# HUB-USB.net
KiCad netlist of a schematic drawn in Altium Designer
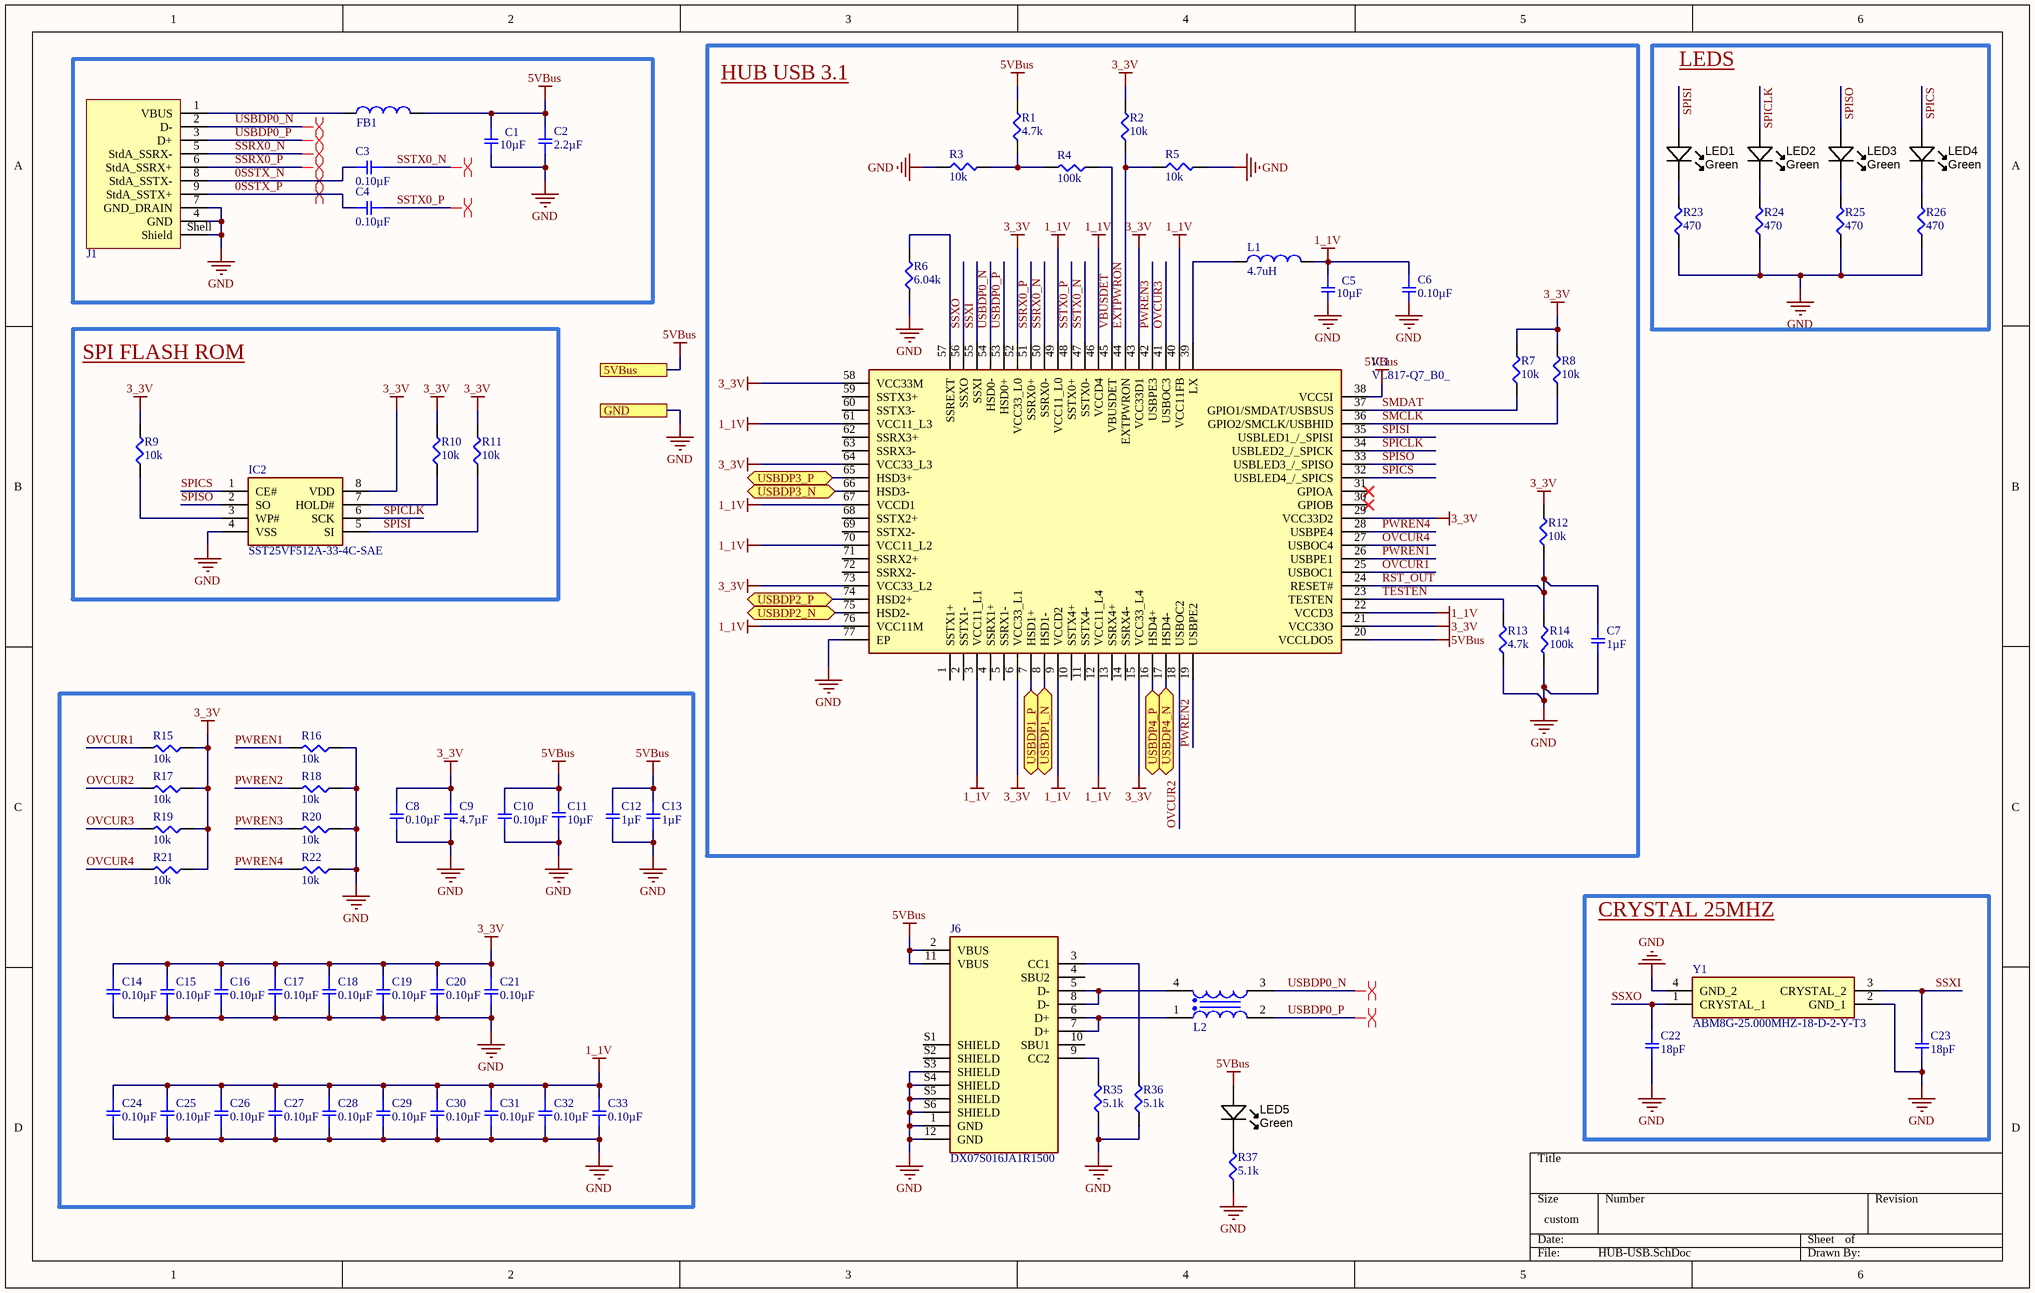
[diagram p0: HUB-USB.SchDoc]

(export (version "E")
  (design (tool "Eeschema 10.0.6"))
  (components
    (comp (ref "C1")
      (value "10µF")
      (footprint "SMD-0603C")
      (description "CAP CER 10UF 16V X6S 0603")
      (fields
        (field (name "PART NUMBER") "GRT188C81C106ME13D")
        (field (name "DIGI-KEY PART NUMBER") "490-12286-1-ND")
      )
      (libsource (lib "cap_murata") (part "CAPACITOR"))
    )
    (comp (ref "C2")
      (value "2.2µF")
      (footprint "SMD-0603C")
      (description "CAP CER 2.2UF 16V X6S 0603")
      (fields
        (field (name "PART NUMBER") "GRT188C81C225KE13D")
        (field (name "DIGI-KEY PART NUMBER") "490-12287-1-ND")
      )
      (libsource (lib "cap_murata") (part "CAPACITOR"))
    )
    (comp (ref "C3")
      (value "0.10µF")
      (footprint "SMD-0402C")
      (description "CAP CER 0.1UF 16V X7R 0402")
      (fields
        (field (name "PART NUMBER") "GCM155R71C104KA55J")
        (field (name "DIGI-KEY PART NUMBER") "490-7998-1-ND")
      )
      (libsource (lib "cap_murata") (part "CAPACITOR"))
    )
    (comp (ref "C4")
      (value "0.10µF")
      (footprint "SMD-0402C")
      (description "CAP CER 0.1UF 16V X7R 0402")
      (fields
        (field (name "PART NUMBER") "GCM155R71C104KA55J")
        (field (name "DIGI-KEY PART NUMBER") "490-7998-1-ND")
      )
      (libsource (lib "cap_murata") (part "CAPACITOR"))
    )
    (comp (ref "C5")
      (value "10µF")
      (footprint "SMD-0603C")
      (description "CAP CER 10UF 16V X6S 0603")
      (fields
        (field (name "PART NUMBER") "GRT188C81C106ME13D")
        (field (name "DIGI-KEY PART NUMBER") "490-12286-1-ND")
      )
      (libsource (lib "cap_murata") (part "CAPACITOR"))
    )
    (comp (ref "C6")
      (value "0.10µF")
      (footprint "SMD-0402C")
      (description "CAP CER 0.1UF 16V X7R 0402")
      (fields
        (field (name "PART NUMBER") "GCM155R71C104KA55J")
        (field (name "DIGI-KEY PART NUMBER") "490-7998-1-ND")
      )
      (libsource (lib "cap_murata") (part "CAPACITOR"))
    )
    (comp (ref "C7")
      (value "1µF")
      (footprint "SMD-0402C")
      (description "CAP CER 1UF 25V X5R 0402")
      (fields
        (field (name "PART NUMBER") "GRM155R61E105MA12D")
        (field (name "DIGI-KEY PART NUMBER") "490-10018-1-ND")
      )
      (libsource (lib "cap_murata") (part "CAPACITOR"))
    )
    (comp (ref "C8")
      (value "0.10µF")
      (footprint "SMD-0402C")
      (description "CAP CER 0.1UF 16V X7R 0402")
      (fields
        (field (name "PART NUMBER") "GCM155R71C104KA55J")
        (field (name "DIGI-KEY PART NUMBER") "490-7998-1-ND")
      )
      (libsource (lib "cap_murata") (part "CAPACITOR"))
    )
    (comp (ref "C9")
      (value "4.7µF")
      (footprint "SMD-0402C")
      (description "CAP CER 4.7UF 10V X5R 0402")
      (fields
        (field (name "PART NUMBER") "ZRB15XR61A475KE01D")
        (field (name "DIGI-KEY PART NUMBER") "490-13252-1-ND")
      )
      (libsource (lib "cap_murata") (part "CAPACITOR"))
    )
    (comp (ref "C10")
      (value "0.10µF")
      (footprint "SMD-0402C")
      (description "CAP CER 0.1UF 16V X7R 0402")
      (fields
        (field (name "PART NUMBER") "GCM155R71C104KA55J")
        (field (name "DIGI-KEY PART NUMBER") "490-7998-1-ND")
      )
      (libsource (lib "cap_murata") (part "CAPACITOR"))
    )
    (comp (ref "C11")
      (value "10µF")
      (footprint "SMD-0805C")
      (description "CAP CER 10UF 16V X6S 0805")
      (fields
        (field (name "PART NUMBER") "GRT21BC81C106KE01L")
        (field (name "DIGI-KEY PART NUMBER") "490-12343-1-ND")
      )
      (libsource (lib "cap_murata") (part "CAPACITOR"))
    )
    (comp (ref "C12")
      (value "1µF")
      (footprint "SMD-0402C")
      (description "CAP CER 1UF 25V X5R 0402")
      (fields
        (field (name "PART NUMBER") "GRM155R61E105MA12D")
        (field (name "DIGI-KEY PART NUMBER") "490-10018-1-ND")
      )
      (libsource (lib "cap_murata") (part "CAPACITOR"))
    )
    (comp (ref "C13")
      (value "1µF")
      (footprint "SMD-0402C")
      (description "CAP CER 1UF 25V X5R 0402")
      (fields
        (field (name "PART NUMBER") "GRM155R61E105MA12D")
        (field (name "DIGI-KEY PART NUMBER") "490-10018-1-ND")
      )
      (libsource (lib "cap_murata") (part "CAPACITOR"))
    )
    (comp (ref "C14")
      (value "0.10µF")
      (footprint "SMD-0402C")
      (description "CAP CER 0.1UF 16V X7R 0402")
      (fields
        (field (name "PART NUMBER") "GCM155R71C104KA55J")
        (field (name "DIGI-KEY PART NUMBER") "490-7998-1-ND")
      )
      (libsource (lib "cap_murata") (part "CAPACITOR"))
    )
    (comp (ref "C15")
      (value "0.10µF")
      (footprint "SMD-0402C")
      (description "CAP CER 0.1UF 16V X7R 0402")
      (fields
        (field (name "PART NUMBER") "GCM155R71C104KA55J")
        (field (name "DIGI-KEY PART NUMBER") "490-7998-1-ND")
      )
      (libsource (lib "cap_murata") (part "CAPACITOR"))
    )
    (comp (ref "C16")
      (value "0.10µF")
      (footprint "SMD-0402C")
      (description "CAP CER 0.1UF 16V X7R 0402")
      (fields
        (field (name "PART NUMBER") "GCM155R71C104KA55J")
        (field (name "DIGI-KEY PART NUMBER") "490-7998-1-ND")
      )
      (libsource (lib "cap_murata") (part "CAPACITOR"))
    )
    (comp (ref "C17")
      (value "0.10µF")
      (footprint "SMD-0402C")
      (description "CAP CER 0.1UF 16V X7R 0402")
      (fields
        (field (name "PART NUMBER") "GCM155R71C104KA55J")
        (field (name "DIGI-KEY PART NUMBER") "490-7998-1-ND")
      )
      (libsource (lib "cap_murata") (part "CAPACITOR"))
    )
    (comp (ref "C18")
      (value "0.10µF")
      (footprint "SMD-0402C")
      (description "CAP CER 0.1UF 16V X7R 0402")
      (fields
        (field (name "PART NUMBER") "GCM155R71C104KA55J")
        (field (name "DIGI-KEY PART NUMBER") "490-7998-1-ND")
      )
      (libsource (lib "cap_murata") (part "CAPACITOR"))
    )
    (comp (ref "C19")
      (value "0.10µF")
      (footprint "SMD-0402C")
      (description "CAP CER 0.1UF 16V X7R 0402")
      (fields
        (field (name "PART NUMBER") "GCM155R71C104KA55J")
        (field (name "DIGI-KEY PART NUMBER") "490-7998-1-ND")
      )
      (libsource (lib "cap_murata") (part "CAPACITOR"))
    )
    (comp (ref "C20")
      (value "0.10µF")
      (footprint "SMD-0402C")
      (description "CAP CER 0.1UF 16V X7R 0402")
      (fields
        (field (name "PART NUMBER") "GCM155R71C104KA55J")
        (field (name "DIGI-KEY PART NUMBER") "490-7998-1-ND")
      )
      (libsource (lib "cap_murata") (part "CAPACITOR"))
    )
    (comp (ref "C21")
      (value "0.10µF")
      (footprint "SMD-0402C")
      (description "CAP CER 0.1UF 16V X7R 0402")
      (fields
        (field (name "PART NUMBER") "GCM155R71C104KA55J")
        (field (name "DIGI-KEY PART NUMBER") "490-7998-1-ND")
      )
      (libsource (lib "cap_murata") (part "CAPACITOR"))
    )
    (comp (ref "C22")
      (value "18pF")
      (footprint "SMD-0402C")
      (description "CAP CER 18PF 25V NP0 0402")
      (fields
        (field (name "PART NUMBER") "GRM1555C1E180JA01D")
        (field (name "DIGI-KEY PART NUMBER") "490-6172-1-ND")
      )
      (libsource (lib "cap_murata") (part "CAPACITOR"))
    )
    (comp (ref "C23")
      (value "18pF")
      (footprint "SMD-0402C")
      (description "CAP CER 18PF 25V NP0 0402")
      (fields
        (field (name "PART NUMBER") "GRM1555C1E180JA01D")
        (field (name "DIGI-KEY PART NUMBER") "490-6172-1-ND")
      )
      (libsource (lib "cap_murata") (part "CAPACITOR"))
    )
    (comp (ref "C24")
      (value "0.10µF")
      (footprint "SMD-0402C")
      (description "CAP CER 0.1UF 16V X7R 0402")
      (fields
        (field (name "PART NUMBER") "GCM155R71C104KA55J")
        (field (name "DIGI-KEY PART NUMBER") "490-7998-1-ND")
      )
      (libsource (lib "cap_murata") (part "CAPACITOR"))
    )
    (comp (ref "C25")
      (value "0.10µF")
      (footprint "SMD-0402C")
      (description "CAP CER 0.1UF 16V X7R 0402")
      (fields
        (field (name "PART NUMBER") "GCM155R71C104KA55J")
        (field (name "DIGI-KEY PART NUMBER") "490-7998-1-ND")
      )
      (libsource (lib "cap_murata") (part "CAPACITOR"))
    )
    (comp (ref "C26")
      (value "0.10µF")
      (footprint "SMD-0402C")
      (description "CAP CER 0.1UF 16V X7R 0402")
      (fields
        (field (name "PART NUMBER") "GCM155R71C104KA55J")
        (field (name "DIGI-KEY PART NUMBER") "490-7998-1-ND")
      )
      (libsource (lib "cap_murata") (part "CAPACITOR"))
    )
    (comp (ref "C27")
      (value "0.10µF")
      (footprint "SMD-0402C")
      (description "CAP CER 0.1UF 16V X7R 0402")
      (fields
        (field (name "PART NUMBER") "GCM155R71C104KA55J")
        (field (name "DIGI-KEY PART NUMBER") "490-7998-1-ND")
      )
      (libsource (lib "cap_murata") (part "CAPACITOR"))
    )
    (comp (ref "C28")
      (value "0.10µF")
      (footprint "SMD-0402C")
      (description "CAP CER 0.1UF 16V X7R 0402")
      (fields
        (field (name "PART NUMBER") "GCM155R71C104KA55J")
        (field (name "DIGI-KEY PART NUMBER") "490-7998-1-ND")
      )
      (libsource (lib "cap_murata") (part "CAPACITOR"))
    )
    (comp (ref "C29")
      (value "0.10µF")
      (footprint "SMD-0402C")
      (description "CAP CER 0.1UF 16V X7R 0402")
      (fields
        (field (name "PART NUMBER") "GCM155R71C104KA55J")
        (field (name "DIGI-KEY PART NUMBER") "490-7998-1-ND")
      )
      (libsource (lib "cap_murata") (part "CAPACITOR"))
    )
    (comp (ref "C30")
      (value "0.10µF")
      (footprint "SMD-0402C")
      (description "CAP CER 0.1UF 16V X7R 0402")
      (fields
        (field (name "PART NUMBER") "GCM155R71C104KA55J")
        (field (name "DIGI-KEY PART NUMBER") "490-7998-1-ND")
      )
      (libsource (lib "cap_murata") (part "CAPACITOR"))
    )
    (comp (ref "C31")
      (value "0.10µF")
      (footprint "SMD-0402C")
      (description "CAP CER 0.1UF 16V X7R 0402")
      (fields
        (field (name "PART NUMBER") "GCM155R71C104KA55J")
        (field (name "DIGI-KEY PART NUMBER") "490-7998-1-ND")
      )
      (libsource (lib "cap_murata") (part "CAPACITOR"))
    )
    (comp (ref "C32")
      (value "0.10µF")
      (footprint "SMD-0402C")
      (description "CAP CER 0.1UF 16V X7R 0402")
      (fields
        (field (name "PART NUMBER") "GCM155R71C104KA55J")
        (field (name "DIGI-KEY PART NUMBER") "490-7998-1-ND")
      )
      (libsource (lib "cap_murata") (part "CAPACITOR"))
    )
    (comp (ref "C33")
      (value "0.10µF")
      (footprint "SMD-0402C")
      (description "CAP CER 0.1UF 16V X7R 0402")
      (fields
        (field (name "PART NUMBER") "GCM155R71C104KA55J")
        (field (name "DIGI-KEY PART NUMBER") "490-7998-1-ND")
      )
      (libsource (lib "cap_murata") (part "CAPACITOR"))
    )
    (comp (ref "FB1")
      (value "10Ohm")
      (footprint "WE-CBA_0402_L1W0.5H0.5_HC")
      (description "WE-CBA SMT EMI Suppression Ferrite Bead, size 0402, 10Ohm, 1.5A")
      (fields
        (field (name "MANUFACTURER PART NUMBER") "782423100")
        (field (name "MANUFACTURER") "Wurth Elektronik")
      )
      (libsource (lib "Altium_WE-CBA (rev22d)") (part "782423100"))
    )
    (comp (ref "IC1")
      (value "VL817-Q7_B0_")
      (footprint "SamacSys:QFN40P900X900X90-77N-D")
      (description "Integrated Circuit")
      (fields (field (name "MANUFACTURER_PART_NUMBER") "VL817-Q7(B0)"))
      (libsource (lib "SamacSys") (part "VL817-Q7_B0_"))
    )
    (comp (ref "IC2")
      (value "SST25VF512A-33-4C-SAE")
      (footprint "SamacSys:SOIC127P600X175-8N")
      (description "Integrated Circuit")
      (fields (field (name "MOUSER PART NUMBER") "804-25VF512A3CSAE"))
      (libsource (lib "SamacSys") (part "SST25VF512A-33-4C-SAE"))
    )
    (comp (ref "J1")
      (value "692122030100")
      (footprint "692122030100")
      (description "WR-COM USB 3.0 Type A Horizontal SMT")
      (fields (field (name "MANUFACTURER") "Wurth Elektronik"))
      (libsource (lib "Altium_WR-USB (rev23b)") (part "692122030100"))
    )
    (comp (ref "J6")
      (value "DX07S016JA1R1500")
      (footprint "JAE_DX07S016JA1R1500")
      (libsource (lib "DX07S016JA1R1500") (part "DX07S016JA1R1500"))
    )
    (comp (ref "L1")
      (value "4.7uH")
      (footprint "INDC2518X200N")
      (description "Ind Power Chip Wirewound 4.7uH 20% 7.96MHz Ferrite 1.1A 1007 T/R")
      (fields (field (name "MP") "CB2518T4R7M"))
      (libsource (lib "DSD_Aerobits_RPI4_OLED") (part "CB2518T4R7M"))
    )
    (comp (ref "L2")
      (value "90Ohm")
      (footprint "WE-CNSW_1206")
      (description "WE-CNSW SMT Common Mode Line Filter, size 1206, 90Ohm, 0.111uH, 50V")
      (fields
        (field (name "MANUFACTURER") "Wurth Elektronik")
        (field (name "MANUFACTURER PART NUMBER") "744232090")
      )
      (libsource (lib "WE-CNSW (rev22a)") (part "744232090"))
    )
    (comp (ref "LED1")
      (value "Green")
      (footprint "LED-0603-GREEN")
      (description "LED 0603 SMD Green 525nm 350mcd 20mA")
      (libsource (lib "PBL - Light Sources") (part "LED_SMD_Green_0603_525nm_350mcd"))
    )
    (comp (ref "LED2")
      (value "Green")
      (footprint "LED-0603-GREEN")
      (description "LED 0603 SMD Green 525nm 350mcd 20mA")
      (libsource (lib "PBL - Light Sources") (part "LED_SMD_Green_0603_525nm_350mcd"))
    )
    (comp (ref "LED3")
      (value "Green")
      (footprint "LED-0603-GREEN")
      (description "LED 0603 SMD Green 525nm 350mcd 20mA")
      (libsource (lib "PBL - Light Sources") (part "LED_SMD_Green_0603_525nm_350mcd"))
    )
    (comp (ref "LED4")
      (value "Green")
      (footprint "LED-0603-GREEN")
      (description "LED 0603 SMD Green 525nm 350mcd 20mA")
      (libsource (lib "PBL - Light Sources") (part "LED_SMD_Green_0603_525nm_350mcd"))
    )
    (comp (ref "LED5")
      (value "Green")
      (footprint "LED-0603-GREEN")
      (description "LED 0603 SMD Green 570nm 50mcd 20mA")
      (libsource (lib "PBL - Light Sources") (part "LED_SMD_Green_0603_570nm"))
    )
    (comp (ref "R1")
      (value "4.7k")
      (footprint "SMD-0402-RES")
      (description "RES SMD 4.7K OHM 1% 1/10W 0402")
      (fields
        (field (name "PART NUMBER") "ERJ-2RKF4701X")
        (field (name "DIGI-KEY PART NUMBER") "P4.70KLCT-ND")
      )
      (libsource (lib "res_panasonic_erj_xls") (part "RESISTOR"))
    )
    (comp (ref "R2")
      (value "10k")
      (footprint "SMD-0402-RES")
      (description "RES SMD 10K OHM 1% 1/10W 0402")
      (fields
        (field (name "PART NUMBER") "ERJ-2RKF1002X")
        (field (name "DIGI-KEY PART NUMBER") "P10.0KLCT-ND")
      )
      (libsource (lib "res_panasonic_erj_xls") (part "RESISTOR"))
    )
    (comp (ref "R3")
      (value "10k")
      (footprint "SMD-0402-RES")
      (description "RES SMD 10K OHM 1% 1/10W 0402")
      (fields
        (field (name "PART NUMBER") "ERJ-2RKF1002X")
        (field (name "DIGI-KEY PART NUMBER") "P10.0KLCT-ND")
      )
      (libsource (lib "res_panasonic_erj_xls") (part "RESISTOR"))
    )
    (comp (ref "R4")
      (value "100k")
      (footprint "SMD-0402-RES")
      (description "RES SMD 100K OHM 1% 1/10W 0402")
      (fields
        (field (name "PART NUMBER") "ERJ-2RKF1003X")
        (field (name "DIGI-KEY PART NUMBER") "P100KLCT-ND")
      )
      (libsource (lib "res_panasonic_erj_xls") (part "RESISTOR"))
    )
    (comp (ref "R5")
      (value "10k")
      (footprint "SMD-0402-RES")
      (description "RES SMD 10K OHM 1% 1/10W 0402")
      (fields
        (field (name "PART NUMBER") "ERJ-2RKF1002X")
        (field (name "DIGI-KEY PART NUMBER") "P10.0KLCT-ND")
      )
      (libsource (lib "res_panasonic_erj_xls") (part "RESISTOR"))
    )
    (comp (ref "R6")
      (value "6.04k")
      (footprint "SMD-0402-RES")
      (description "RES SMD 6.04K OHM 1% 1/10W 0402")
      (fields
        (field (name "PART NUMBER") "ERJ-2RKF6041X")
        (field (name "DIGI-KEY PART NUMBER") "P6.04KLCT-ND")
      )
      (libsource (lib "res_panasonic_erj_xls") (part "RESISTOR"))
    )
    (comp (ref "R7")
      (value "10k")
      (footprint "SMD-0402-RES")
      (description "RES SMD 10K OHM 1% 1/10W 0402")
      (fields
        (field (name "PART NUMBER") "ERJ-2RKF1002X")
        (field (name "DIGI-KEY PART NUMBER") "P10.0KLCT-ND")
      )
      (libsource (lib "res_panasonic_erj_xls") (part "RESISTOR"))
    )
    (comp (ref "R8")
      (value "10k")
      (footprint "SMD-0402-RES")
      (description "RES SMD 10K OHM 1% 1/10W 0402")
      (fields
        (field (name "PART NUMBER") "ERJ-2RKF1002X")
        (field (name "DIGI-KEY PART NUMBER") "P10.0KLCT-ND")
      )
      (libsource (lib "res_panasonic_erj_xls") (part "RESISTOR"))
    )
    (comp (ref "R9")
      (value "10k")
      (footprint "SMD-0402-RES")
      (description "RES SMD 10K OHM 1% 1/10W 0402")
      (fields
        (field (name "PART NUMBER") "ERJ-2RKF1002X")
        (field (name "DIGI-KEY PART NUMBER") "P10.0KLCT-ND")
      )
      (libsource (lib "res_panasonic_erj_xls") (part "RESISTOR"))
    )
    (comp (ref "R10")
      (value "10k")
      (footprint "SMD-0402-RES")
      (description "RES SMD 10K OHM 1% 1/10W 0402")
      (fields
        (field (name "PART NUMBER") "ERJ-2RKF1002X")
        (field (name "DIGI-KEY PART NUMBER") "P10.0KLCT-ND")
      )
      (libsource (lib "res_panasonic_erj_xls") (part "RESISTOR"))
    )
    (comp (ref "R11")
      (value "10k")
      (footprint "SMD-0402-RES")
      (description "RES SMD 10K OHM 1% 1/10W 0402")
      (fields
        (field (name "PART NUMBER") "ERJ-2RKF1002X")
        (field (name "DIGI-KEY PART NUMBER") "P10.0KLCT-ND")
      )
      (libsource (lib "res_panasonic_erj_xls") (part "RESISTOR"))
    )
    (comp (ref "R12")
      (value "10k")
      (footprint "SMD-0402-RES")
      (description "RES SMD 10K OHM 1% 1/10W 0402")
      (fields
        (field (name "PART NUMBER") "ERJ-2RKF1002X")
        (field (name "DIGI-KEY PART NUMBER") "P10.0KLCT-ND")
      )
      (libsource (lib "res_panasonic_erj_xls") (part "RESISTOR"))
    )
    (comp (ref "R13")
      (value "4.7k")
      (footprint "SMD-0402-RES")
      (description "RES SMD 4.7K OHM 1% 1/10W 0402")
      (fields
        (field (name "PART NUMBER") "ERJ-2RKF4701X")
        (field (name "DIGI-KEY PART NUMBER") "P4.70KLCT-ND")
      )
      (libsource (lib "res_panasonic_erj_xls") (part "RESISTOR"))
    )
    (comp (ref "R14")
      (value "100k")
      (footprint "SMD-0402-RES")
      (description "RES SMD 100K OHM 1% 1/10W 0402")
      (fields
        (field (name "PART NUMBER") "ERJ-2RKF1003X")
        (field (name "DIGI-KEY PART NUMBER") "P100KLCT-ND")
      )
      (libsource (lib "res_panasonic_erj_xls") (part "RESISTOR"))
    )
    (comp (ref "R15")
      (value "10k")
      (footprint "SMD-0402-RES")
      (description "RES SMD 10K OHM 1% 1/10W 0402")
      (fields
        (field (name "PART NUMBER") "ERJ-2RKF1002X")
        (field (name "DIGI-KEY PART NUMBER") "P10.0KLCT-ND")
      )
      (libsource (lib "res_panasonic_erj_xls") (part "RESISTOR"))
    )
    (comp (ref "R16")
      (value "10k")
      (footprint "SMD-0402-RES")
      (description "RES SMD 10K OHM 1% 1/10W 0402")
      (fields
        (field (name "PART NUMBER") "ERJ-2RKF1002X")
        (field (name "DIGI-KEY PART NUMBER") "P10.0KLCT-ND")
      )
      (libsource (lib "res_panasonic_erj_xls") (part "RESISTOR"))
    )
    (comp (ref "R17")
      (value "10k")
      (footprint "SMD-0402-RES")
      (description "RES SMD 10K OHM 1% 1/10W 0402")
      (fields
        (field (name "PART NUMBER") "ERJ-2RKF1002X")
        (field (name "DIGI-KEY PART NUMBER") "P10.0KLCT-ND")
      )
      (libsource (lib "res_panasonic_erj_xls") (part "RESISTOR"))
    )
    (comp (ref "R18")
      (value "10k")
      (footprint "SMD-0402-RES")
      (description "RES SMD 10K OHM 1% 1/10W 0402")
      (fields
        (field (name "PART NUMBER") "ERJ-2RKF1002X")
        (field (name "DIGI-KEY PART NUMBER") "P10.0KLCT-ND")
      )
      (libsource (lib "res_panasonic_erj_xls") (part "RESISTOR"))
    )
    (comp (ref "R19")
      (value "10k")
      (footprint "SMD-0402-RES")
      (description "RES SMD 10K OHM 1% 1/10W 0402")
      (fields
        (field (name "PART NUMBER") "ERJ-2RKF1002X")
        (field (name "DIGI-KEY PART NUMBER") "P10.0KLCT-ND")
      )
      (libsource (lib "res_panasonic_erj_xls") (part "RESISTOR"))
    )
    (comp (ref "R20")
      (value "10k")
      (footprint "SMD-0402-RES")
      (description "RES SMD 10K OHM 1% 1/10W 0402")
      (fields
        (field (name "PART NUMBER") "ERJ-2RKF1002X")
        (field (name "DIGI-KEY PART NUMBER") "P10.0KLCT-ND")
      )
      (libsource (lib "res_panasonic_erj_xls") (part "RESISTOR"))
    )
    (comp (ref "R21")
      (value "10k")
      (footprint "SMD-0402-RES")
      (description "RES SMD 10K OHM 1% 1/10W 0402")
      (fields
        (field (name "PART NUMBER") "ERJ-2RKF1002X")
        (field (name "DIGI-KEY PART NUMBER") "P10.0KLCT-ND")
      )
      (libsource (lib "res_panasonic_erj_xls") (part "RESISTOR"))
    )
    (comp (ref "R22")
      (value "10k")
      (footprint "SMD-0402-RES")
      (description "RES SMD 10K OHM 1% 1/10W 0402")
      (fields
        (field (name "PART NUMBER") "ERJ-2RKF1002X")
        (field (name "DIGI-KEY PART NUMBER") "P10.0KLCT-ND")
      )
      (libsource (lib "res_panasonic_erj_xls") (part "RESISTOR"))
    )
    (comp (ref "R23")
      (value "470")
      (footprint "SMD-0402-RES")
      (description "RES SMD 470 OHM 5% 1/10W 0402")
      (fields (field (name "PART NUMBER") "ERJ-2GEJ471X") (field (name "DIGI-KEY PART NUMBER") "P470JCT-ND"))
      (libsource (lib "res_panasonic_erj_xls") (part "RESISTOR"))
    )
    (comp (ref "R24")
      (value "470")
      (footprint "SMD-0402-RES")
      (description "RES SMD 470 OHM 5% 1/10W 0402")
      (fields (field (name "PART NUMBER") "ERJ-2GEJ471X") (field (name "DIGI-KEY PART NUMBER") "P470JCT-ND"))
      (libsource (lib "res_panasonic_erj_xls") (part "RESISTOR"))
    )
    (comp (ref "R25")
      (value "470")
      (footprint "SMD-0402-RES")
      (description "RES SMD 470 OHM 5% 1/10W 0402")
      (fields (field (name "PART NUMBER") "ERJ-2GEJ471X") (field (name "DIGI-KEY PART NUMBER") "P470JCT-ND"))
      (libsource (lib "res_panasonic_erj_xls") (part "RESISTOR"))
    )
    (comp (ref "R26")
      (value "470")
      (footprint "SMD-0402-RES")
      (description "RES SMD 470 OHM 5% 1/10W 0402")
      (fields (field (name "PART NUMBER") "ERJ-2GEJ471X") (field (name "DIGI-KEY PART NUMBER") "P470JCT-ND"))
      (libsource (lib "res_panasonic_erj_xls") (part "RESISTOR"))
    )
    (comp (ref "R35")
      (value "5.1k")
      (footprint "SMD-0603-RES")
      (description "RES SMD 5.1K OHM 1% 1/10W 0603")
      (fields
        (field (name "PART NUMBER") "ERJ-3EKF5101V")
        (field (name "DIGI-KEY PART NUMBER") "P5.10KHCT-ND")
      )
      (libsource (lib "res_panasonic_erj_xls") (part "RESISTOR"))
    )
    (comp (ref "R36")
      (value "5.1k")
      (footprint "SMD-0603-RES")
      (description "RES SMD 5.1K OHM 1% 1/10W 0603")
      (fields
        (field (name "PART NUMBER") "ERJ-3EKF5101V")
        (field (name "DIGI-KEY PART NUMBER") "P5.10KHCT-ND")
      )
      (libsource (lib "res_panasonic_erj_xls") (part "RESISTOR"))
    )
    (comp (ref "R37")
      (value "5.1k")
      (footprint "SMD-0603-RES")
      (description "RES SMD 5.1K OHM 1% 1/10W 0603")
      (fields
        (field (name "PART NUMBER") "ERJ-3EKF5101V")
        (field (name "DIGI-KEY PART NUMBER") "P5.10KHCT-ND")
      )
      (libsource (lib "res_panasonic_erj_xls") (part "RESISTOR"))
    )
    (comp (ref "Y1")
      (value "ABM8G-25.000MHZ-18-D-2-Y-T3")
      (footprint "SamacSys:ABM8G16000MHZB4YT")
      (description "Crystal or Oscillator")
      (libsource (lib "SamacSys") (part "ABM8G-25.000MHZ-18-D-2-Y-T3"))
    )
  )
  (nets
    (net (code "1") (name "/0SSTX_N") (class "Default")
      (node (ref "C3") (pin "2") (pinfunction "2_2") (pintype "passive"))
      (node (ref "J1") (pin "8") (pinfunction "StdA_SSTX-_8") (pintype "passive"))
    )
    (net (code "2") (name "/0SSTX_P") (class "Default")
      (node (ref "C4") (pin "2") (pinfunction "2_2") (pintype "passive"))
      (node (ref "J1") (pin "9") (pinfunction "StdA_SSTX+_9") (pintype "passive"))
    )
    (net (code "3") (name "/EXTPWRON") (class "Default")
      (node (ref "IC1") (pin "44") (pinfunction "EXTPWRON_44") (pintype "passive"))
      (node (ref "R2") (pin "1") (pinfunction "1_1") (pintype "passive"))
      (node (ref "R5") (pin "1") (pinfunction "1_1") (pintype "passive"))
    )
    (net (code "4") (name "/OVCUR1") (class "Default")
      (node (ref "IC1") (pin "25") (pinfunction "USBOC1_25") (pintype "passive"))
      (node (ref "R15") (pin "2") (pinfunction "2_2") (pintype "passive"))
    )
    (net (code "5") (name "/OVCUR2") (class "Default")
      (node (ref "IC1") (pin "18") (pinfunction "USBOC2_18") (pintype "passive"))
      (node (ref "R17") (pin "2") (pinfunction "2_2") (pintype "passive"))
    )
    (net (code "6") (name "/OVCUR3") (class "Default")
      (node (ref "IC1") (pin "41") (pinfunction "USBOC3_41") (pintype "passive"))
      (node (ref "R19") (pin "2") (pinfunction "2_2") (pintype "passive"))
    )
    (net (code "7") (name "/OVCUR4") (class "Default")
      (node (ref "IC1") (pin "27") (pinfunction "USBOC4_27") (pintype "passive"))
      (node (ref "R21") (pin "2") (pinfunction "2_2") (pintype "passive"))
    )
    (net (code "8") (name "/PWREN1") (class "Default")
      (node (ref "IC1") (pin "26") (pinfunction "USBPE1_26") (pintype "passive"))
      (node (ref "R16") (pin "2") (pinfunction "2_2") (pintype "passive"))
    )
    (net (code "9") (name "/PWREN2") (class "Default")
      (node (ref "IC1") (pin "19") (pinfunction "USBPE2_19") (pintype "passive"))
      (node (ref "R18") (pin "2") (pinfunction "2_2") (pintype "passive"))
    )
    (net (code "10") (name "/PWREN3") (class "Default")
      (node (ref "IC1") (pin "42") (pinfunction "USBPE3_42") (pintype "passive"))
      (node (ref "R20") (pin "2") (pinfunction "2_2") (pintype "passive"))
    )
    (net (code "11") (name "/PWREN4") (class "Default")
      (node (ref "IC1") (pin "28") (pinfunction "USBPE4_28") (pintype "passive"))
      (node (ref "R22") (pin "2") (pinfunction "2_2") (pintype "passive"))
    )
    (net (code "12") (name "/RST_OUT") (class "Default")
      (node (ref "C7") (pin "1") (pinfunction "1_1") (pintype "passive"))
      (node (ref "IC1") (pin "24") (pinfunction "RESET#_24") (pintype "passive"))
      (node (ref "R12") (pin "1") (pinfunction "1_1") (pintype "passive"))
      (node (ref "R14") (pin "1") (pinfunction "1_1") (pintype "passive"))
    )
    (net (code "13") (name "/SMCLK") (class "Default")
      (node (ref "IC1") (pin "36") (pinfunction "GPIO2/SMCLK/USBHID_36") (pintype "passive"))
      (node (ref "R8") (pin "1") (pinfunction "1_1") (pintype "passive"))
    )
    (net (code "14") (name "/SMDAT") (class "Default")
      (node (ref "IC1") (pin "37") (pinfunction "GPIO1/SMDAT/USBSUS_37") (pintype "passive"))
      (node (ref "R7") (pin "1") (pinfunction "1_1") (pintype "passive"))
    )
    (net (code "15") (name "/SPICLK") (class "Default")
      (node (ref "IC1") (pin "34") (pinfunction "USBLED2_/_SPICK_34") (pintype "passive"))
      (node (ref "IC2") (pin "6") (pinfunction "SCK_6") (pintype "passive"))
      (node (ref "LED2") (pin "A") (pinfunction "A_A") (pintype "passive"))
    )
    (net (code "16") (name "/SPICS") (class "Default")
      (node (ref "IC1") (pin "32") (pinfunction "USBLED4_/_SPICS_32") (pintype "passive"))
      (node (ref "IC2") (pin "1") (pinfunction "CE#_1") (pintype "passive"))
      (node (ref "LED4") (pin "A") (pinfunction "A_A") (pintype "passive"))
    )
    (net (code "17") (name "/SPISI") (class "Default")
      (node (ref "IC1") (pin "35") (pinfunction "USBLED1_/_SPISI_35") (pintype "passive"))
      (node (ref "IC2") (pin "5") (pinfunction "SI_5") (pintype "passive"))
      (node (ref "LED1") (pin "A") (pinfunction "A_A") (pintype "passive"))
      (node (ref "R11") (pin "1") (pinfunction "1_1") (pintype "passive"))
    )
    (net (code "18") (name "/SPISO") (class "Default")
      (node (ref "IC1") (pin "33") (pinfunction "USBLED3_/_SPISO_33") (pintype "passive"))
      (node (ref "IC2") (pin "2") (pinfunction "SO_2") (pintype "passive"))
      (node (ref "LED3") (pin "A") (pinfunction "A_A") (pintype "passive"))
    )
    (net (code "19") (name "/SSRX0_N") (class "Default")
      (node (ref "IC1") (pin "50") (pinfunction "SSRX0-_50") (pintype "passive"))
      (node (ref "J1") (pin "5") (pinfunction "StdA_SSRX-_5") (pintype "passive"))
    )
    (net (code "20") (name "/SSRX0_P") (class "Default")
      (node (ref "IC1") (pin "51") (pinfunction "SSRX0+_51") (pintype "passive"))
      (node (ref "J1") (pin "6") (pinfunction "StdA_SSRX+_6") (pintype "passive"))
    )
    (net (code "21") (name "/SSTX0_N") (class "Default")
      (node (ref "C3") (pin "1") (pinfunction "1_1") (pintype "passive"))
      (node (ref "IC1") (pin "47") (pinfunction "SSTX0-_47") (pintype "passive"))
    )
    (net (code "22") (name "/SSTX0_P") (class "Default")
      (node (ref "C4") (pin "1") (pinfunction "1_1") (pintype "passive"))
      (node (ref "IC1") (pin "48") (pinfunction "SSTX0+_48") (pintype "passive"))
    )
    (net (code "23") (name "/SSXI") (class "Default")
      (node (ref "C23") (pin "1") (pinfunction "1_1") (pintype "passive"))
      (node (ref "IC1") (pin "55") (pinfunction "SSXI_55") (pintype "passive"))
      (node (ref "Y1") (pin "3") (pinfunction "CRYSTAL_2_3") (pintype "passive"))
    )
    (net (code "24") (name "/SSXO") (class "Default")
      (node (ref "C22") (pin "1") (pinfunction "1_1") (pintype "passive"))
      (node (ref "IC1") (pin "56") (pinfunction "SSXO_56") (pintype "passive"))
      (node (ref "Y1") (pin "1") (pinfunction "CRYSTAL_1_1") (pintype "passive"))
    )
    (net (code "25") (name "/TESTEN") (class "Default")
      (node (ref "IC1") (pin "23") (pinfunction "TESTEN_23") (pintype "passive"))
      (node (ref "R13") (pin "2") (pinfunction "2_2") (pintype "passive"))
    )
    (net (code "26") (name "/USBDP0_N") (class "Default")
      (node (ref "IC1") (pin "54") (pinfunction "HSD0-_54") (pintype "passive"))
      (node (ref "J1") (pin "2") (pinfunction "D-_2") (pintype "passive"))
      (node (ref "L2") (pin "3") (pinfunction "3_3") (pintype "passive"))
    )
    (net (code "27") (name "/USBDP0_P") (class "Default")
      (node (ref "IC1") (pin "53") (pinfunction "HSD0+_53") (pintype "passive"))
      (node (ref "J1") (pin "3") (pinfunction "D+_3") (pintype "passive"))
      (node (ref "L2") (pin "2") (pinfunction "2_2") (pintype "passive"))
    )
    (net (code "28") (name "/USBDP1_N") (class "Default")
      (node (ref "IC1") (pin "8") (pinfunction "HSD1-_8") (pintype "passive"))
    )
    (net (code "29") (name "/USBDP1_P") (class "Default")
      (node (ref "IC1") (pin "7") (pinfunction "HSD1+_7") (pintype "passive"))
    )
    (net (code "30") (name "/USBDP2_N") (class "Default")
      (node (ref "IC1") (pin "75") (pinfunction "HSD2-_75") (pintype "passive"))
    )
    (net (code "31") (name "/USBDP2_P") (class "Default")
      (node (ref "IC1") (pin "74") (pinfunction "HSD2+_74") (pintype "passive"))
    )
    (net (code "32") (name "/USBDP3_N") (class "Default")
      (node (ref "IC1") (pin "66") (pinfunction "HSD3-_66") (pintype "passive"))
    )
    (net (code "33") (name "/USBDP3_P") (class "Default")
      (node (ref "IC1") (pin "65") (pinfunction "HSD3+_65") (pintype "passive"))
    )
    (net (code "34") (name "/USBDP4_N") (class "Default")
      (node (ref "IC1") (pin "17") (pinfunction "HSD4-_17") (pintype "passive"))
    )
    (net (code "35") (name "/USBDP4_P") (class "Default")
      (node (ref "IC1") (pin "16") (pinfunction "HSD4+_16") (pintype "passive"))
    )
    (net (code "36") (name "/VBUSDET") (class "Default")
      (node (ref "IC1") (pin "45") (pinfunction "VBUSDET_45") (pintype "passive"))
      (node (ref "R4") (pin "1") (pinfunction "1_1") (pintype "passive"))
    )
    (net (code "37") (name "1_1V") (class "Default")
      (node (ref "C24") (pin "1") (pinfunction "1_1") (pintype "passive"))
      (node (ref "C25") (pin "1") (pinfunction "1_1") (pintype "passive"))
      (node (ref "C26") (pin "1") (pinfunction "1_1") (pintype "passive"))
      (node (ref "C27") (pin "1") (pinfunction "1_1") (pintype "passive"))
      (node (ref "C28") (pin "1") (pinfunction "1_1") (pintype "passive"))
      (node (ref "C29") (pin "1") (pinfunction "1_1") (pintype "passive"))
      (node (ref "C30") (pin "1") (pinfunction "1_1") (pintype "passive"))
      (node (ref "C31") (pin "1") (pinfunction "1_1") (pintype "passive"))
      (node (ref "C32") (pin "1") (pinfunction "1_1") (pintype "passive"))
      (node (ref "C33") (pin "1") (pinfunction "1_1") (pintype "passive"))
      (node (ref "C5") (pin "1") (pinfunction "1_1") (pintype "passive"))
      (node (ref "C6") (pin "1") (pinfunction "1_1") (pintype "passive"))
      (node (ref "IC1") (pin "12") (pinfunction "VCC11_L4_12") (pintype "passive"))
      (node (ref "IC1") (pin "22") (pinfunction "VCCD3_22") (pintype "passive"))
      (node (ref "IC1") (pin "3") (pinfunction "VCC11_L1_3") (pintype "passive"))
      (node (ref "IC1") (pin "40") (pinfunction "VCC11FB_40") (pintype "passive"))
      (node (ref "IC1") (pin "46") (pinfunction "VCCD4_46") (pintype "passive"))
      (node (ref "IC1") (pin "49") (pinfunction "VCC11_L0_49") (pintype "passive"))
      (node (ref "IC1") (pin "61") (pinfunction "VCC11_L3_61") (pintype "passive"))
      (node (ref "IC1") (pin "67") (pinfunction "VCCD1_67") (pintype "passive"))
      (node (ref "IC1") (pin "70") (pinfunction "VCC11_L2_70") (pintype "passive"))
      (node (ref "IC1") (pin "76") (pinfunction "VCC11M_76") (pintype "passive"))
      (node (ref "IC1") (pin "9") (pinfunction "VCCD2_9") (pintype "passive"))
      (node (ref "L1") (pin "2") (pinfunction "2_2") (pintype "passive"))
    )
    (net (code "38") (name "3_3V") (class "Default")
      (node (ref "C14") (pin "1") (pinfunction "1_1") (pintype "passive"))
      (node (ref "C15") (pin "1") (pinfunction "1_1") (pintype "passive"))
      (node (ref "C16") (pin "1") (pinfunction "1_1") (pintype "passive"))
      (node (ref "C17") (pin "1") (pinfunction "1_1") (pintype "passive"))
      (node (ref "C18") (pin "1") (pinfunction "1_1") (pintype "passive"))
      (node (ref "C19") (pin "1") (pinfunction "1_1") (pintype "passive"))
      (node (ref "C20") (pin "1") (pinfunction "1_1") (pintype "passive"))
      (node (ref "C21") (pin "1") (pinfunction "1_1") (pintype "passive"))
      (node (ref "C8") (pin "1") (pinfunction "1_1") (pintype "passive"))
      (node (ref "C9") (pin "1") (pinfunction "1_1") (pintype "passive"))
      (node (ref "IC1") (pin "15") (pinfunction "VCC33_L4_15") (pintype "passive"))
      (node (ref "IC1") (pin "21") (pinfunction "VCC33O_21") (pintype "passive"))
      (node (ref "IC1") (pin "29") (pinfunction "VCC33D2_29") (pintype "passive"))
      (node (ref "IC1") (pin "43") (pinfunction "VCC33D1_43") (pintype "passive"))
      (node (ref "IC1") (pin "52") (pinfunction "VCC33_L0_52") (pintype "passive"))
      (node (ref "IC1") (pin "58") (pinfunction "VCC33M_58") (pintype "passive"))
      (node (ref "IC1") (pin "6") (pinfunction "VCC33_L1_6") (pintype "passive"))
      (node (ref "IC1") (pin "64") (pinfunction "VCC33_L3_64") (pintype "passive"))
      (node (ref "IC1") (pin "73") (pinfunction "VCC33_L2_73") (pintype "passive"))
      (node (ref "IC2") (pin "8") (pinfunction "VDD_8") (pintype "passive"))
      (node (ref "R10") (pin "2") (pinfunction "2_2") (pintype "passive"))
      (node (ref "R11") (pin "2") (pinfunction "2_2") (pintype "passive"))
      (node (ref "R12") (pin "2") (pinfunction "2_2") (pintype "passive"))
      (node (ref "R15") (pin "1") (pinfunction "1_1") (pintype "passive"))
      (node (ref "R17") (pin "1") (pinfunction "1_1") (pintype "passive"))
      (node (ref "R19") (pin "1") (pinfunction "1_1") (pintype "passive"))
      (node (ref "R2") (pin "2") (pinfunction "2_2") (pintype "passive"))
      (node (ref "R21") (pin "1") (pinfunction "1_1") (pintype "passive"))
      (node (ref "R7") (pin "2") (pinfunction "2_2") (pintype "passive"))
      (node (ref "R8") (pin "2") (pinfunction "2_2") (pintype "passive"))
      (node (ref "R9") (pin "2") (pinfunction "2_2") (pintype "passive"))
    )
    (net (code "39") (name "5VBus") (class "Default")
      (node (ref "C1") (pin "1") (pinfunction "1_1") (pintype "passive"))
      (node (ref "C10") (pin "1") (pinfunction "1_1") (pintype "passive"))
      (node (ref "C11") (pin "2") (pinfunction "2_2") (pintype "passive"))
      (node (ref "C12") (pin "1") (pinfunction "1_1") (pintype "passive"))
      (node (ref "C13") (pin "1") (pinfunction "1_1") (pintype "passive"))
      (node (ref "C2") (pin "1") (pinfunction "1_1") (pintype "passive"))
      (node (ref "FB1") (pin "2") (pinfunction "2_2") (pintype "passive"))
      (node (ref "IC1") (pin "20") (pinfunction "VCCLDO5_20") (pintype "passive"))
      (node (ref "IC1") (pin "38") (pinfunction "VCC5I_38") (pintype "passive"))
      (node (ref "J6") (pin "11") (pinfunction "VBUS_11") (pintype "power_in"))
      (node (ref "J6") (pin "2") (pinfunction "VBUS_2") (pintype "power_in"))
      (node (ref "LED5") (pin "A") (pinfunction "A_A") (pintype "passive"))
      (node (ref "R1") (pin "2") (pinfunction "2_2") (pintype "passive"))
    )
    (net (code "40") (name "GND") (class "Default")
      (node (ref "C1") (pin "2") (pinfunction "2_2") (pintype "passive"))
      (node (ref "C10") (pin "2") (pinfunction "2_2") (pintype "passive"))
      (node (ref "C11") (pin "1") (pinfunction "1_1") (pintype "passive"))
      (node (ref "C12") (pin "2") (pinfunction "2_2") (pintype "passive"))
      (node (ref "C13") (pin "2") (pinfunction "2_2") (pintype "passive"))
      (node (ref "C14") (pin "2") (pinfunction "2_2") (pintype "passive"))
      (node (ref "C15") (pin "2") (pinfunction "2_2") (pintype "passive"))
      (node (ref "C16") (pin "2") (pinfunction "2_2") (pintype "passive"))
      (node (ref "C17") (pin "2") (pinfunction "2_2") (pintype "passive"))
      (node (ref "C18") (pin "2") (pinfunction "2_2") (pintype "passive"))
      (node (ref "C19") (pin "2") (pinfunction "2_2") (pintype "passive"))
      (node (ref "C2") (pin "2") (pinfunction "2_2") (pintype "passive"))
      (node (ref "C20") (pin "2") (pinfunction "2_2") (pintype "passive"))
      (node (ref "C21") (pin "2") (pinfunction "2_2") (pintype "passive"))
      (node (ref "C22") (pin "2") (pinfunction "2_2") (pintype "passive"))
      (node (ref "C23") (pin "2") (pinfunction "2_2") (pintype "passive"))
      (node (ref "C24") (pin "2") (pinfunction "2_2") (pintype "passive"))
      (node (ref "C25") (pin "2") (pinfunction "2_2") (pintype "passive"))
      (node (ref "C26") (pin "2") (pinfunction "2_2") (pintype "passive"))
      (node (ref "C27") (pin "2") (pinfunction "2_2") (pintype "passive"))
      (node (ref "C28") (pin "2") (pinfunction "2_2") (pintype "passive"))
      (node (ref "C29") (pin "2") (pinfunction "2_2") (pintype "passive"))
      (node (ref "C30") (pin "2") (pinfunction "2_2") (pintype "passive"))
      (node (ref "C31") (pin "2") (pinfunction "2_2") (pintype "passive"))
      (node (ref "C32") (pin "2") (pinfunction "2_2") (pintype "passive"))
      (node (ref "C33") (pin "2") (pinfunction "2_2") (pintype "passive"))
      (node (ref "C5") (pin "2") (pinfunction "2_2") (pintype "passive"))
      (node (ref "C6") (pin "2") (pinfunction "2_2") (pintype "passive"))
      (node (ref "C7") (pin "2") (pinfunction "2_2") (pintype "passive"))
      (node (ref "C8") (pin "2") (pinfunction "2_2") (pintype "passive"))
      (node (ref "C9") (pin "2") (pinfunction "2_2") (pintype "passive"))
      (node (ref "IC1") (pin "77") (pinfunction "EP_77") (pintype "passive"))
      (node (ref "IC2") (pin "4") (pinfunction "VSS_4") (pintype "passive"))
      (node (ref "J1") (pin "4") (pinfunction "GND_4") (pintype "passive"))
      (node (ref "J1") (pin "7") (pinfunction "GND_DRAIN_7") (pintype "passive"))
      (node (ref "J1") (pin "Shell") (pinfunction "Shield_Shell") (pintype "passive"))
      (node (ref "J6") (pin "1") (pinfunction "GND_1") (pintype "power_in"))
      (node (ref "J6") (pin "12") (pinfunction "GND_12") (pintype "power_in"))
      (node (ref "J6") (pin "S3") (pinfunction "SHIELD_S3") (pintype "passive"))
      (node (ref "J6") (pin "S4") (pinfunction "SHIELD_S4") (pintype "passive"))
      (node (ref "J6") (pin "S5") (pinfunction "SHIELD_S5") (pintype "passive"))
      (node (ref "J6") (pin "S6") (pinfunction "SHIELD_S6") (pintype "passive"))
      (node (ref "R13") (pin "1") (pinfunction "1_1") (pintype "passive"))
      (node (ref "R14") (pin "2") (pinfunction "2_2") (pintype "passive"))
      (node (ref "R16") (pin "1") (pinfunction "1_1") (pintype "passive"))
      (node (ref "R18") (pin "1") (pinfunction "1_1") (pintype "passive"))
      (node (ref "R20") (pin "1") (pinfunction "1_1") (pintype "passive"))
      (node (ref "R22") (pin "1") (pinfunction "1_1") (pintype "passive"))
      (node (ref "R23") (pin "1") (pinfunction "1_1") (pintype "passive"))
      (node (ref "R24") (pin "1") (pinfunction "1_1") (pintype "passive"))
      (node (ref "R25") (pin "1") (pinfunction "1_1") (pintype "passive"))
      (node (ref "R26") (pin "1") (pinfunction "1_1") (pintype "passive"))
      (node (ref "R3") (pin "1") (pinfunction "1_1") (pintype "passive"))
      (node (ref "R35") (pin "1") (pinfunction "1_1") (pintype "passive"))
      (node (ref "R36") (pin "1") (pinfunction "1_1") (pintype "passive"))
      (node (ref "R37") (pin "1") (pinfunction "1_1") (pintype "passive"))
      (node (ref "R5") (pin "2") (pinfunction "2_2") (pintype "passive"))
      (node (ref "R6") (pin "1") (pinfunction "1_1") (pintype "passive"))
      (node (ref "Y1") (pin "2") (pinfunction "GND_1_2") (pintype "passive"))
      (node (ref "Y1") (pin "4") (pinfunction "GND_2_4") (pintype "passive"))
    )
    (net (code "41") (name "Net-(IC1-LX)") (class "Default")
      (node (ref "IC1") (pin "39") (pinfunction "LX_39") (pintype "passive"))
      (node (ref "L1") (pin "1") (pinfunction "1_1") (pintype "passive"))
    )
    (net (code "42") (name "Net-(IC1-SSREXT)") (class "Default")
      (node (ref "IC1") (pin "57") (pinfunction "SSREXT_57") (pintype "passive"))
      (node (ref "R6") (pin "2") (pinfunction "2_2") (pintype "passive"))
    )
    (net (code "43") (name "Net-(IC2-HOLD#)") (class "Default")
      (node (ref "IC2") (pin "7") (pinfunction "HOLD#_7") (pintype "passive"))
      (node (ref "R10") (pin "1") (pinfunction "1_1") (pintype "passive"))
    )
    (net (code "44") (name "Net-(IC2-WP#)") (class "Default")
      (node (ref "IC2") (pin "3") (pinfunction "WP#_3") (pintype "passive"))
      (node (ref "R9") (pin "1") (pinfunction "1_1") (pintype "passive"))
    )
    (net (code "45") (name "Net-(J1-VBUS)") (class "Default")
      (node (ref "FB1") (pin "1") (pinfunction "1_1") (pintype "passive"))
      (node (ref "J1") (pin "1") (pinfunction "VBUS_1") (pintype "passive"))
    )
    (net (code "46") (name "Net-(J6-CC1)") (class "Default")
      (node (ref "J6") (pin "3") (pinfunction "CC1_3") (pintype "passive"))
      (node (ref "R36") (pin "2") (pinfunction "2_2") (pintype "passive"))
    )
    (net (code "47") (name "Net-(J6-CC2)") (class "Default")
      (node (ref "J6") (pin "9") (pinfunction "CC2_9") (pintype "passive"))
      (node (ref "R35") (pin "2") (pinfunction "2_2") (pintype "passive"))
    )
    (net (code "48") (name "Net-(J6-D+-Pad6)") (class "Default")
      (node (ref "J6") (pin "6") (pinfunction "D+_6") (pintype "passive"))
      (node (ref "J6") (pin "7") (pinfunction "D+_7") (pintype "passive"))
      (node (ref "L2") (pin "1") (pinfunction "1_1") (pintype "passive"))
    )
    (net (code "49") (name "Net-(J6-D--Pad5)") (class "Default")
      (node (ref "J6") (pin "5") (pinfunction "D-_5") (pintype "passive"))
      (node (ref "J6") (pin "8") (pinfunction "D-_8") (pintype "passive"))
      (node (ref "L2") (pin "4") (pinfunction "4_4") (pintype "passive"))
    )
    (net (code "50") (name "Net-(LED1-PadK)") (class "Default")
      (node (ref "LED1") (pin "K") (pinfunction "K_K") (pintype "passive"))
      (node (ref "R23") (pin "2") (pinfunction "2_2") (pintype "passive"))
    )
    (net (code "51") (name "Net-(LED2-PadK)") (class "Default")
      (node (ref "LED2") (pin "K") (pinfunction "K_K") (pintype "passive"))
      (node (ref "R24") (pin "2") (pinfunction "2_2") (pintype "passive"))
    )
    (net (code "52") (name "Net-(LED3-PadK)") (class "Default")
      (node (ref "LED3") (pin "K") (pinfunction "K_K") (pintype "passive"))
      (node (ref "R25") (pin "2") (pinfunction "2_2") (pintype "passive"))
    )
    (net (code "53") (name "Net-(LED4-PadK)") (class "Default")
      (node (ref "LED4") (pin "K") (pinfunction "K_K") (pintype "passive"))
      (node (ref "R26") (pin "2") (pinfunction "2_2") (pintype "passive"))
    )
    (net (code "54") (name "Net-(LED5-PadK)") (class "Default")
      (node (ref "LED5") (pin "K") (pinfunction "K_K") (pintype "passive"))
      (node (ref "R37") (pin "2") (pinfunction "2_2") (pintype "passive"))
    )
    (net (code "55") (name "Net-(R1-Pad1)") (class "Default")
      (node (ref "R1") (pin "1") (pinfunction "1_1") (pintype "passive"))
      (node (ref "R3") (pin "2") (pinfunction "2_2") (pintype "passive"))
      (node (ref "R4") (pin "2") (pinfunction "2_2") (pintype "passive"))
    )
    (net (code "56") (name "unconnected-(IC1-GPIOA-Pad31)") (class "Default")
      (node (ref "IC1") (pin "31") (pinfunction "GPIOA_31") (pintype "passive+no_connect"))
    )
    (net (code "57") (name "unconnected-(IC1-GPIOB-Pad30)") (class "Default")
      (node (ref "IC1") (pin "30") (pinfunction "GPIOB_30") (pintype "passive+no_connect"))
    )
    (net (code "58") (name "unconnected-(IC1-SSRX1+-Pad4)") (class "Default")
      (node (ref "IC1") (pin "4") (pinfunction "SSRX1+_4") (pintype "passive"))
    )
    (net (code "59") (name "unconnected-(IC1-SSRX1--Pad5)") (class "Default")
      (node (ref "IC1") (pin "5") (pinfunction "SSRX1-_5") (pintype "passive"))
    )
    (net (code "60") (name "unconnected-(IC1-SSRX2+-Pad71)") (class "Default")
      (node (ref "IC1") (pin "71") (pinfunction "SSRX2+_71") (pintype "passive"))
    )
    (net (code "61") (name "unconnected-(IC1-SSRX2--Pad72)") (class "Default")
      (node (ref "IC1") (pin "72") (pinfunction "SSRX2-_72") (pintype "passive"))
    )
    (net (code "62") (name "unconnected-(IC1-SSRX3+-Pad62)") (class "Default")
      (node (ref "IC1") (pin "62") (pinfunction "SSRX3+_62") (pintype "passive"))
    )
    (net (code "63") (name "unconnected-(IC1-SSRX3--Pad63)") (class "Default")
      (node (ref "IC1") (pin "63") (pinfunction "SSRX3-_63") (pintype "passive"))
    )
    (net (code "64") (name "unconnected-(IC1-SSRX4+-Pad13)") (class "Default")
      (node (ref "IC1") (pin "13") (pinfunction "SSRX4+_13") (pintype "passive"))
    )
    (net (code "65") (name "unconnected-(IC1-SSRX4--Pad14)") (class "Default")
      (node (ref "IC1") (pin "14") (pinfunction "SSRX4-_14") (pintype "passive"))
    )
    (net (code "66") (name "unconnected-(IC1-SSTX1+-Pad1)") (class "Default")
      (node (ref "IC1") (pin "1") (pinfunction "SSTX1+_1") (pintype "passive"))
    )
    (net (code "67") (name "unconnected-(IC1-SSTX1--Pad2)") (class "Default")
      (node (ref "IC1") (pin "2") (pinfunction "SSTX1-_2") (pintype "passive"))
    )
    (net (code "68") (name "unconnected-(IC1-SSTX2+-Pad68)") (class "Default")
      (node (ref "IC1") (pin "68") (pinfunction "SSTX2+_68") (pintype "passive"))
    )
    (net (code "69") (name "unconnected-(IC1-SSTX2--Pad69)") (class "Default")
      (node (ref "IC1") (pin "69") (pinfunction "SSTX2-_69") (pintype "passive"))
    )
    (net (code "70") (name "unconnected-(IC1-SSTX3+-Pad59)") (class "Default")
      (node (ref "IC1") (pin "59") (pinfunction "SSTX3+_59") (pintype "passive"))
    )
    (net (code "71") (name "unconnected-(IC1-SSTX3--Pad60)") (class "Default")
      (node (ref "IC1") (pin "60") (pinfunction "SSTX3-_60") (pintype "passive"))
    )
    (net (code "72") (name "unconnected-(IC1-SSTX4+-Pad10)") (class "Default")
      (node (ref "IC1") (pin "10") (pinfunction "SSTX4+_10") (pintype "passive"))
    )
    (net (code "73") (name "unconnected-(IC1-SSTX4--Pad11)") (class "Default")
      (node (ref "IC1") (pin "11") (pinfunction "SSTX4-_11") (pintype "passive"))
    )
    (net (code "74") (name "unconnected-(J6-SBU1-Pad10)") (class "Default")
      (node (ref "J6") (pin "10") (pinfunction "SBU1_10") (pintype "passive"))
    )
    (net (code "75") (name "unconnected-(J6-SBU2-Pad4)") (class "Default")
      (node (ref "J6") (pin "4") (pinfunction "SBU2_4") (pintype "passive"))
    )
    (net (code "76") (name "unconnected-(J6-SHIELD-PadS1)") (class "Default")
      (node (ref "J6") (pin "S1") (pinfunction "SHIELD_S1") (pintype "passive"))
    )
    (net (code "77") (name "unconnected-(J6-SHIELD-PadS2)") (class "Default")
      (node (ref "J6") (pin "S2") (pinfunction "SHIELD_S2") (pintype "passive"))
    )
  )
)
